# MCU.net
KiCad netlist of a schematic drawn in Altium Designer
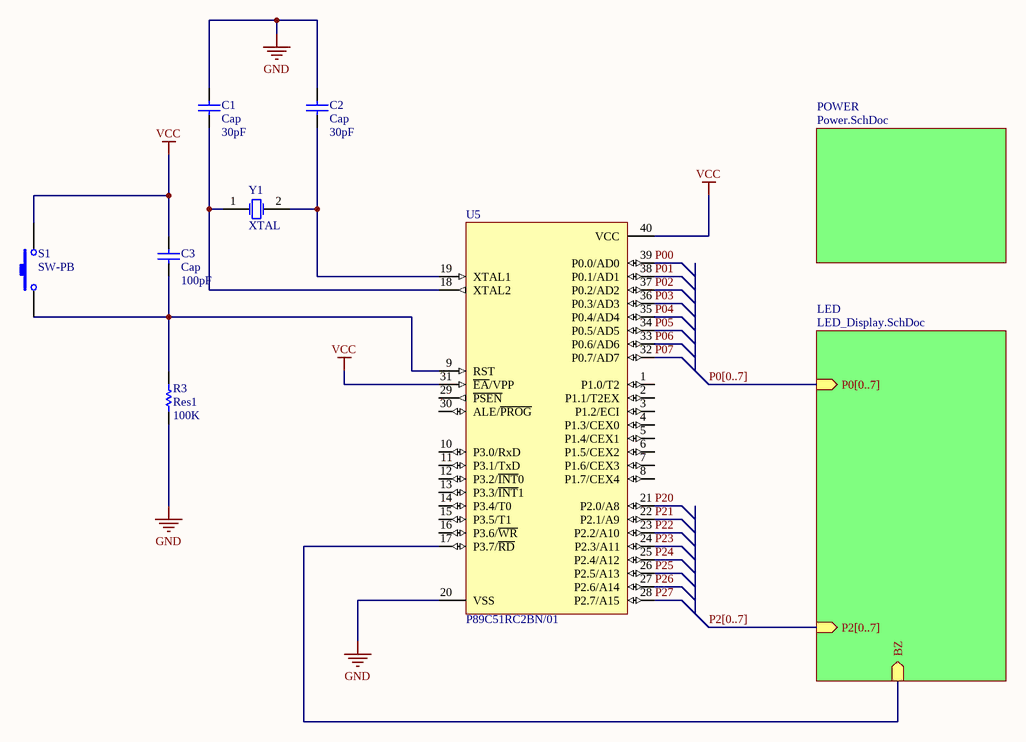
[diagram p0: MCU.SchDoc]

(export (version "E")
  (design (tool "Eeschema 10.0.6"))
  (components
    (comp (ref "C1")
      (value "Cap")
      (footprint "RAD-0.3")
      (description "Capacitor")
      (fields (field (name "ALTIUM_VALUE") "30pF") (field (name "PUBLISHER") "Altium Limited"))
      (libsource (lib "Chap-7-实践题(1)") (part "Cap"))
    )
    (comp (ref "C2")
      (value "Cap")
      (footprint "RAD-0.3")
      (description "Capacitor")
      (fields (field (name "ALTIUM_VALUE") "30pF") (field (name "PUBLISHER") "Altium Limited"))
      (libsource (lib "Chap-7-实践题(1)") (part "Cap"))
    )
    (comp (ref "C3")
      (value "Cap")
      (footprint "RAD-0.3")
      (description "Capacitor")
      (fields (field (name "ALTIUM_VALUE") "100pF") (field (name "PUBLISHER") "Altium Limited"))
      (libsource (lib "Chap-7-实践题(1)") (part "Cap"))
    )
    (comp (ref "R3")
      (value "Res1")
      (footprint "AXIAL-0.3")
      (description "Resistor")
      (fields (field (name "ALTIUM_VALUE") "100K") (field (name "PUBLISHER") "Altium Limited"))
      (libsource (lib "Chap-7-实践题(1)") (part "Res1"))
    )
    (comp (ref "S1")
      (value "SW-PB")
      (footprint "SPST-2")
      (description "Switch")
      (fields (field (name "PUBLISHER") "Altium Limited"))
      (libsource (lib "Chap-7-实践题(1)") (part "SW-PB"))
    )
    (comp (ref "U5")
      (value "P89C51RC2BN/01")
      (footprint "SOT129-1")
      (description "80C51 8-Bit Flash Microcontroller Family, 32 kB ISP/IAP Flash with 512 B RAM.")
      (fields (field (name "PUBLISHER") "Altium Limited"))
      (libsource (lib "Chap-7-实践题(1)") (part "P89C51RC2BN/01"))
    )
    (comp (ref "Y1")
      (value "XTAL")
      (footprint "R38")
      (description "Crystal Oscillator")
      (fields (field (name "PUBLISHER") "Altium Limited"))
      (libsource (lib "Chap-7-实践题(1)") (part "XTAL"))
    )
  )
  (nets
    (net (code "1") (name "/BZ") (class "Default")
      (node (ref "U5") (pin "17") (pinfunction "P3.7/~{RD}_17") (pintype "bidirectional"))
    )
    (net (code "2") (name "/P00") (class "Default")
      (node (ref "U5") (pin "39") (pinfunction "P0.0/AD0_39") (pintype "bidirectional"))
    )
    (net (code "4") (name "/P01") (class "Default")
      (node (ref "U5") (pin "38") (pinfunction "P0.1/AD1_38") (pintype "bidirectional"))
    )
    (net (code "5") (name "/P02") (class "Default")
      (node (ref "U5") (pin "37") (pinfunction "P0.2/AD2_37") (pintype "bidirectional"))
    )
    (net (code "7") (name "/P03") (class "Default")
      (node (ref "U5") (pin "36") (pinfunction "P0.3/AD3_36") (pintype "bidirectional"))
    )
    (net (code "8") (name "/P04") (class "Default")
      (node (ref "U5") (pin "35") (pinfunction "P0.4/AD4_35") (pintype "bidirectional"))
    )
    (net (code "9") (name "/P05") (class "Default")
      (node (ref "U5") (pin "34") (pinfunction "P0.5/AD5_34") (pintype "bidirectional"))
    )
    (net (code "10") (name "/P06") (class "Default")
      (node (ref "U5") (pin "33") (pinfunction "P0.6/AD6_33") (pintype "bidirectional"))
    )
    (net (code "11") (name "/P07") (class "Default")
      (node (ref "U5") (pin "32") (pinfunction "P0.7/AD7_32") (pintype "bidirectional"))
    )
    (net (code "12") (name "/P20") (class "Default")
      (node (ref "U5") (pin "21") (pinfunction "P2.0/A8_21") (pintype "bidirectional"))
    )
    (net (code "13") (name "/P21") (class "Default")
      (node (ref "U5") (pin "22") (pinfunction "P2.1/A9_22") (pintype "bidirectional"))
    )
    (net (code "14") (name "/P22") (class "Default")
      (node (ref "U5") (pin "23") (pinfunction "P2.2/A10_23") (pintype "bidirectional"))
    )
    (net (code "15") (name "/P23") (class "Default")
      (node (ref "U5") (pin "24") (pinfunction "P2.3/A11_24") (pintype "bidirectional"))
    )
    (net (code "16") (name "/P24") (class "Default")
      (node (ref "U5") (pin "25") (pinfunction "P2.4/A12_25") (pintype "bidirectional"))
    )
    (net (code "17") (name "/P25") (class "Default")
      (node (ref "U5") (pin "26") (pinfunction "P2.5/A13_26") (pintype "bidirectional"))
    )
    (net (code "18") (name "/P26") (class "Default")
      (node (ref "U5") (pin "27") (pinfunction "P2.6/A14_27") (pintype "bidirectional"))
    )
    (net (code "19") (name "/P27") (class "Default")
      (node (ref "U5") (pin "28") (pinfunction "P2.7/A15_28") (pintype "bidirectional"))
    )
    (net (code "20") (name "GND") (class "Default")
      (node (ref "C1") (pin "2") (pinfunction "2_2") (pintype "passive"))
      (node (ref "C2") (pin "2") (pinfunction "2_2") (pintype "passive"))
      (node (ref "R3") (pin "1") (pinfunction "1_1") (pintype "passive"))
      (node (ref "U5") (pin "20") (pinfunction "VSS_20") (pintype "power_in"))
    )
    (net (code "21") (name "Net-(U5-RST)") (class "Default")
      (node (ref "C3") (pin "1") (pinfunction "1_1") (pintype "passive"))
      (node (ref "R3") (pin "2") (pinfunction "2_2") (pintype "passive"))
      (node (ref "S1") (pin "1") (pinfunction "1_1") (pintype "passive"))
      (node (ref "U5") (pin "9") (pinfunction "RST_9") (pintype "input"))
    )
    (net (code "22") (name "Net-(U5-XTAL1)") (class "Default")
      (node (ref "C2") (pin "1") (pinfunction "1_1") (pintype "passive"))
      (node (ref "U5") (pin "19") (pinfunction "XTAL1_19") (pintype "input"))
      (node (ref "Y1") (pin "2") (pinfunction "OSC2_2") (pintype "passive"))
    )
    (net (code "23") (name "Net-(U5-XTAL2)") (class "Default")
      (node (ref "C1") (pin "1") (pinfunction "1_1") (pintype "passive"))
      (node (ref "U5") (pin "18") (pinfunction "XTAL2_18") (pintype "output"))
      (node (ref "Y1") (pin "1") (pinfunction "OSC1_1") (pintype "passive"))
    )
    (net (code "24") (name "VCC") (class "Default")
      (node (ref "C3") (pin "2") (pinfunction "2_2") (pintype "passive"))
      (node (ref "S1") (pin "2") (pinfunction "2_2") (pintype "passive"))
      (node (ref "U5") (pin "31") (pinfunction "~{EA}/VPP_31") (pintype "input"))
      (node (ref "U5") (pin "40") (pinfunction "VCC_40") (pintype "power_in"))
    )
    (net (code "25") (name "unconnected-(U5-ALE{slash}~{PROG}-Pad30)") (class "Default")
      (node (ref "U5") (pin "30") (pinfunction "ALE/~{PROG}_30") (pintype "bidirectional"))
    )
    (net (code "26") (name "unconnected-(U5-P1.0{slash}T2-Pad1)") (class "Default")
      (node (ref "U5") (pin "1") (pinfunction "P1.0/T2_1") (pintype "bidirectional"))
    )
    (net (code "27") (name "unconnected-(U5-P1.1{slash}T2EX-Pad2)") (class "Default")
      (node (ref "U5") (pin "2") (pinfunction "P1.1/T2EX_2") (pintype "bidirectional"))
    )
    (net (code "28") (name "unconnected-(U5-P1.2{slash}ECI-Pad3)") (class "Default")
      (node (ref "U5") (pin "3") (pinfunction "P1.2/ECI_3") (pintype "bidirectional"))
    )
    (net (code "29") (name "unconnected-(U5-P1.3{slash}CEX0-Pad4)") (class "Default")
      (node (ref "U5") (pin "4") (pinfunction "P1.3/CEX0_4") (pintype "bidirectional"))
    )
    (net (code "30") (name "unconnected-(U5-P1.4{slash}CEX1-Pad5)") (class "Default")
      (node (ref "U5") (pin "5") (pinfunction "P1.4/CEX1_5") (pintype "bidirectional"))
    )
    (net (code "31") (name "unconnected-(U5-P1.5{slash}CEX2-Pad6)") (class "Default")
      (node (ref "U5") (pin "6") (pinfunction "P1.5/CEX2_6") (pintype "bidirectional"))
    )
    (net (code "32") (name "unconnected-(U5-P1.6{slash}CEX3-Pad7)") (class "Default")
      (node (ref "U5") (pin "7") (pinfunction "P1.6/CEX3_7") (pintype "bidirectional"))
    )
    (net (code "33") (name "unconnected-(U5-P1.7{slash}CEX4-Pad8)") (class "Default")
      (node (ref "U5") (pin "8") (pinfunction "P1.7/CEX4_8") (pintype "bidirectional"))
    )
    (net (code "34") (name "unconnected-(U5-P3.0{slash}RxD-Pad10)") (class "Default")
      (node (ref "U5") (pin "10") (pinfunction "P3.0/RxD_10") (pintype "bidirectional"))
    )
    (net (code "35") (name "unconnected-(U5-P3.1{slash}TxD-Pad11)") (class "Default")
      (node (ref "U5") (pin "11") (pinfunction "P3.1/TxD_11") (pintype "bidirectional"))
    )
    (net (code "36") (name "unconnected-(U5-P3.2{slash}~{INT}0-Pad12)") (class "Default")
      (node (ref "U5") (pin "12") (pinfunction "P3.2/~{INT}0_12") (pintype "bidirectional"))
    )
    (net (code "37") (name "unconnected-(U5-P3.3{slash}~{INT}1-Pad13)") (class "Default")
      (node (ref "U5") (pin "13") (pinfunction "P3.3/~{INT}1_13") (pintype "bidirectional"))
    )
    (net (code "38") (name "unconnected-(U5-P3.4{slash}T0-Pad14)") (class "Default")
      (node (ref "U5") (pin "14") (pinfunction "P3.4/T0_14") (pintype "bidirectional"))
    )
    (net (code "39") (name "unconnected-(U5-P3.5{slash}T1-Pad15)") (class "Default")
      (node (ref "U5") (pin "15") (pinfunction "P3.5/T1_15") (pintype "bidirectional"))
    )
    (net (code "40") (name "unconnected-(U5-P3.6{slash}~{WR}-Pad16)") (class "Default")
      (node (ref "U5") (pin "16") (pinfunction "P3.6/~{WR}_16") (pintype "bidirectional"))
    )
    (net (code "41") (name "unconnected-(U5-~{PSEN}-Pad29)") (class "Default")
      (node (ref "U5") (pin "29") (pinfunction "~{PSEN}_29") (pintype "output"))
    )
  )
)
